# untitled.net
KiCad netlist of a schematic drawn in EAGLE
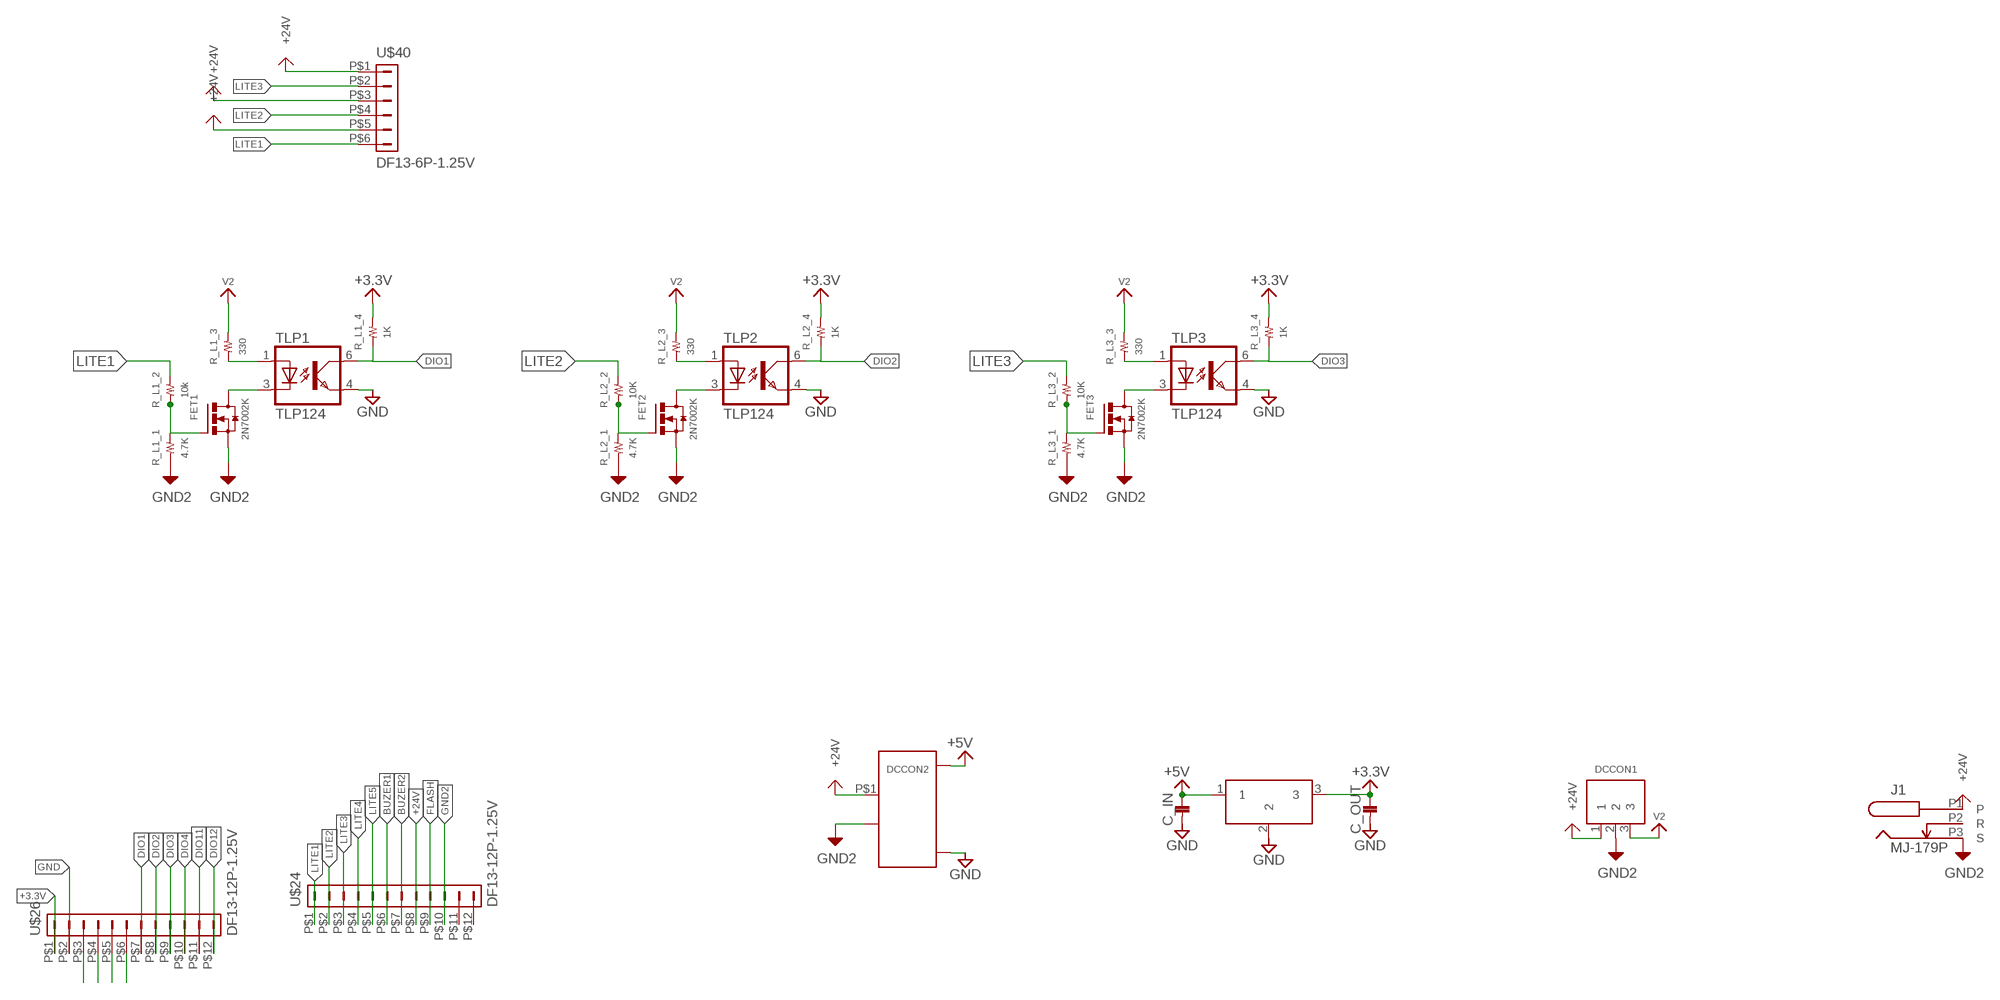
[diagram p0: schematic, sheet 1]

(export (version "E")
  (design (tool "Eeschema 10.0.6"))
  (components
    (comp (ref "C_IN")
      (value "1608")
      (footprint "eagle-import:1608")
      (libsource (lib "eagle-import") (part "1608"))
    )
    (comp (ref "C_OUT")
      (value "1608")
      (footprint "eagle-import:1608")
      (libsource (lib "eagle-import") (part "1608"))
    )
    (comp (ref "DCCON1")
      (value "Ｒ－７８Ｅ５．０")
      (footprint "eagle-import:Ｒ－７８Ｅ５．０")
      (libsource (lib "eagle-import") (part "Ｒ－７８Ｅ５．０"))
    )
    (comp (ref "DCCON2")
      (value "MAU100")
      (footprint "eagle-import:MAU")
      (libsource (lib "eagle-import") (part "MAU100"))
    )
    (comp (ref "FET1")
      (value "2N7002K")
      (footprint "eagle-import:SOT23")
      (libsource (lib "eagle-import") (part "CHIP_FET"))
    )
    (comp (ref "FET2")
      (value "2N7002K")
      (footprint "eagle-import:SOT23")
      (libsource (lib "eagle-import") (part "CHIP_FET"))
    )
    (comp (ref "FET3")
      (value "2N7002K")
      (footprint "eagle-import:SOT23")
      (libsource (lib "eagle-import") (part "CHIP_FET"))
    )
    (comp (ref "J1")
      (value "MJ-179P")
      (footprint "eagle-import:MJ-179P")
      (libsource (lib "eagle-import") (part "MJ-179P"))
    )
    (comp (ref "REGULATOR")
      (value "NJM2845")
      (footprint "eagle-import:TO252")
      (libsource (lib "eagle-import") (part "NJM2845"))
    )
    (comp (ref "R_L1_1")
      (value "4.7K")
      (footprint "eagle-import:1608")
      (libsource (lib "eagle-import") (part "RESISTOR__SMD"))
    )
    (comp (ref "R_L1_2")
      (value "10k")
      (footprint "eagle-import:1608")
      (libsource (lib "eagle-import") (part "RESISTOR__SMD"))
    )
    (comp (ref "R_L1_3")
      (value "330")
      (footprint "eagle-import:1608")
      (libsource (lib "eagle-import") (part "RESISTOR__SMD"))
    )
    (comp (ref "R_L1_4")
      (value "1K")
      (footprint "eagle-import:1608")
      (libsource (lib "eagle-import") (part "RESISTOR__SMD"))
    )
    (comp (ref "R_L2_1")
      (value "4.7K")
      (footprint "eagle-import:1608")
      (libsource (lib "eagle-import") (part "RESISTOR__SMD"))
    )
    (comp (ref "R_L2_2")
      (value "10K")
      (footprint "eagle-import:1608")
      (libsource (lib "eagle-import") (part "RESISTOR__SMD"))
    )
    (comp (ref "R_L2_3")
      (value "330")
      (footprint "eagle-import:1608")
      (libsource (lib "eagle-import") (part "RESISTOR__SMD"))
    )
    (comp (ref "R_L2_4")
      (value "1K")
      (footprint "eagle-import:1608")
      (libsource (lib "eagle-import") (part "RESISTOR__SMD"))
    )
    (comp (ref "R_L3_1")
      (value "4.7K")
      (footprint "eagle-import:1608")
      (libsource (lib "eagle-import") (part "RESISTOR__SMD"))
    )
    (comp (ref "R_L3_2")
      (value "10K")
      (footprint "eagle-import:1608")
      (libsource (lib "eagle-import") (part "RESISTOR__SMD"))
    )
    (comp (ref "R_L3_3")
      (value "330")
      (footprint "eagle-import:1608")
      (libsource (lib "eagle-import") (part "RESISTOR__SMD"))
    )
    (comp (ref "R_L3_4")
      (value "1K")
      (footprint "eagle-import:1608")
      (libsource (lib "eagle-import") (part "RESISTOR__SMD"))
    )
    (comp (ref "TLP1")
      (value "TLP124")
      (footprint "eagle-import:11−4C1")
      (libsource (lib "eagle-import") (part "TLP124"))
    )
    (comp (ref "TLP2")
      (value "TLP124")
      (footprint "eagle-import:11−4C1")
      (libsource (lib "eagle-import") (part "TLP124"))
    )
    (comp (ref "TLP3")
      (value "TLP124")
      (footprint "eagle-import:11−4C1")
      (libsource (lib "eagle-import") (part "TLP124"))
    )
    (comp (ref "U$24")
      (value "DF13-12P-1.25V")
      (footprint "eagle-import:DF13C-12P-1.25V")
      (libsource (lib "eagle-import") (part "DF13-12P-1.25V"))
    )
    (comp (ref "U$26")
      (value "DF13-12P-1.25V")
      (footprint "eagle-import:DF13C-12P-1.25V")
      (libsource (lib "eagle-import") (part "DF13-12P-1.25V"))
    )
    (comp (ref "U$40")
      (value "DF13-6P-1.25V")
      (footprint "eagle-import:DF13C-6P-1.25V")
      (libsource (lib "eagle-import") (part "DF13-6P-1.25V"))
    )
  )
  (nets
    (net (code "1") (name "+3.3V") (class "Default")
      (node (ref "C_OUT") (pin "P$1") (pinfunction "1_P$1") (pintype "passive"))
      (node (ref "REGULATOR") (pin "3") (pinfunction "3_3") (pintype "power_in"))
      (node (ref "R_L1_4") (pin "2") (pinfunction "P$2_2") (pintype "passive"))
      (node (ref "R_L2_4") (pin "2") (pinfunction "P$2_2") (pintype "passive"))
      (node (ref "R_L3_4") (pin "2") (pinfunction "P$2_2") (pintype "passive"))
      (node (ref "U$26") (pin "P$1") (pinfunction "1_P$1") (pintype "passive"))
    )
    (net (code "2") (name "+5V") (class "Default")
      (node (ref "C_IN") (pin "P$1") (pinfunction "1_P$1") (pintype "passive"))
      (node (ref "DCCON2") (pin "P$3") (pinfunction "VO+_P$3") (pintype "bidirectional"))
      (node (ref "REGULATOR") (pin "1") (pinfunction "1_1") (pintype "power_in"))
    )
    (net (code "3") (name "+24V") (class "Default")
      (node (ref "DCCON1") (pin "1") (pinfunction "1_1") (pintype "bidirectional"))
      (node (ref "DCCON2") (pin "P$1") (pinfunction "VIN+_P$1") (pintype "bidirectional"))
      (node (ref "J1") (pin "P1") (pinfunction "P_P1") (pintype "power_in"))
      (node (ref "U$24") (pin "P$8") (pinfunction "8_P$8") (pintype "passive"))
      (node (ref "U$40") (pin "P$1") (pinfunction "1_P$1") (pintype "passive"))
      (node (ref "U$40") (pin "P$3") (pinfunction "3_P$3") (pintype "passive"))
      (node (ref "U$40") (pin "P$5") (pinfunction "5_P$5") (pintype "passive"))
    )
    (net (code "4") (name "BUZER1") (class "Default")
      (node (ref "U$24") (pin "P$6") (pinfunction "6_P$6") (pintype "passive"))
    )
    (net (code "5") (name "BUZER2") (class "Default")
      (node (ref "U$24") (pin "P$7") (pinfunction "7_P$7") (pintype "passive"))
    )
    (net (code "6") (name "DIO1") (class "Default")
      (node (ref "R_L1_4") (pin "1") (pinfunction "P$1_1") (pintype "passive"))
      (node (ref "TLP1") (pin "6") (pinfunction "COL_6") (pintype "passive"))
      (node (ref "U$26") (pin "P$7") (pinfunction "7_P$7") (pintype "passive"))
    )
    (net (code "7") (name "DIO2") (class "Default")
      (node (ref "R_L2_4") (pin "1") (pinfunction "P$1_1") (pintype "passive"))
      (node (ref "TLP2") (pin "6") (pinfunction "COL_6") (pintype "passive"))
      (node (ref "U$26") (pin "P$8") (pinfunction "8_P$8") (pintype "passive"))
    )
    (net (code "8") (name "DIO3") (class "Default")
      (node (ref "R_L3_4") (pin "1") (pinfunction "P$1_1") (pintype "passive"))
      (node (ref "TLP3") (pin "6") (pinfunction "COL_6") (pintype "passive"))
      (node (ref "U$26") (pin "P$9") (pinfunction "9_P$9") (pintype "passive"))
    )
    (net (code "9") (name "DIO4") (class "Default")
      (node (ref "U$26") (pin "P$10") (pinfunction "10_P$10") (pintype "passive"))
    )
    (net (code "10") (name "DIO11") (class "Default")
      (node (ref "U$26") (pin "P$11") (pinfunction "11_P$11") (pintype "passive"))
    )
    (net (code "11") (name "DIO12") (class "Default")
      (node (ref "U$26") (pin "P$12") (pinfunction "12_P$12") (pintype "passive"))
    )
    (net (code "12") (name "FLASH") (class "Default")
      (node (ref "U$24") (pin "P$9") (pinfunction "9_P$9") (pintype "passive"))
    )
    (net (code "13") (name "GND") (class "Default")
      (node (ref "C_IN") (pin "P$2") (pinfunction "2_P$2") (pintype "passive"))
      (node (ref "C_OUT") (pin "P$2") (pinfunction "2_P$2") (pintype "passive"))
      (node (ref "DCCON2") (pin "P$5") (pinfunction "VO-_P$5") (pintype "bidirectional"))
      (node (ref "REGULATOR") (pin "2") (pinfunction "2_2") (pintype "power_in"))
      (node (ref "TLP1") (pin "4") (pinfunction "EMIT_4") (pintype "passive"))
      (node (ref "TLP2") (pin "4") (pinfunction "EMIT_4") (pintype "passive"))
      (node (ref "TLP3") (pin "4") (pinfunction "EMIT_4") (pintype "passive"))
      (node (ref "U$26") (pin "P$2") (pinfunction "2_P$2") (pintype "passive"))
    )
    (net (code "14") (name "GND2") (class "Default")
      (node (ref "DCCON1") (pin "2") (pinfunction "2_2") (pintype "bidirectional"))
      (node (ref "DCCON2") (pin "P$2") (pinfunction "VIN-_P$2") (pintype "bidirectional"))
      (node (ref "FET1") (pin "2") (pinfunction "S_2") (pintype "passive"))
      (node (ref "FET2") (pin "2") (pinfunction "S_2") (pintype "passive"))
      (node (ref "FET3") (pin "2") (pinfunction "S_2") (pintype "passive"))
      (node (ref "J1") (pin "P3") (pinfunction "S_P3") (pintype "power_in"))
      (node (ref "R_L1_1") (pin "1") (pinfunction "P$1_1") (pintype "passive"))
      (node (ref "R_L2_1") (pin "1") (pinfunction "P$1_1") (pintype "passive"))
      (node (ref "R_L3_1") (pin "1") (pinfunction "P$1_1") (pintype "passive"))
      (node (ref "U$24") (pin "P$10") (pinfunction "10_P$10") (pintype "passive"))
    )
    (net (code "15") (name "LITE1") (class "Default")
      (node (ref "R_L1_2") (pin "2") (pinfunction "P$2_2") (pintype "passive"))
      (node (ref "U$24") (pin "P$1") (pinfunction "1_P$1") (pintype "passive"))
      (node (ref "U$40") (pin "P$6") (pinfunction "6_P$6") (pintype "passive"))
    )
    (net (code "16") (name "LITE2") (class "Default")
      (node (ref "R_L2_2") (pin "2") (pinfunction "P$2_2") (pintype "passive"))
      (node (ref "U$24") (pin "P$2") (pinfunction "2_P$2") (pintype "passive"))
      (node (ref "U$40") (pin "P$4") (pinfunction "4_P$4") (pintype "passive"))
    )
    (net (code "17") (name "LITE3") (class "Default")
      (node (ref "R_L3_2") (pin "2") (pinfunction "P$2_2") (pintype "passive"))
      (node (ref "U$24") (pin "P$3") (pinfunction "3_P$3") (pintype "passive"))
      (node (ref "U$40") (pin "P$2") (pinfunction "2_P$2") (pintype "passive"))
    )
    (net (code "18") (name "LITE4") (class "Default")
      (node (ref "U$24") (pin "P$4") (pinfunction "4_P$4") (pintype "passive"))
    )
    (net (code "19") (name "LITE5") (class "Default")
      (node (ref "U$24") (pin "P$5") (pinfunction "5_P$5") (pintype "passive"))
    )
    (net (code "20") (name "Net-(FET1-D)") (class "Default")
      (node (ref "FET1") (pin "3") (pinfunction "D_3") (pintype "passive"))
      (node (ref "TLP1") (pin "3") (pinfunction "C_3") (pintype "passive"))
    )
    (net (code "21") (name "Net-(FET1-G)") (class "Default")
      (node (ref "FET1") (pin "1") (pinfunction "G_1") (pintype "passive"))
      (node (ref "R_L1_1") (pin "2") (pinfunction "P$2_2") (pintype "passive"))
      (node (ref "R_L1_2") (pin "1") (pinfunction "P$1_1") (pintype "passive"))
    )
    (net (code "22") (name "Net-(FET2-D)") (class "Default")
      (node (ref "FET2") (pin "3") (pinfunction "D_3") (pintype "passive"))
      (node (ref "TLP2") (pin "3") (pinfunction "C_3") (pintype "passive"))
    )
    (net (code "23") (name "Net-(FET2-G)") (class "Default")
      (node (ref "FET2") (pin "1") (pinfunction "G_1") (pintype "passive"))
      (node (ref "R_L2_1") (pin "2") (pinfunction "P$2_2") (pintype "passive"))
      (node (ref "R_L2_2") (pin "1") (pinfunction "P$1_1") (pintype "passive"))
    )
    (net (code "24") (name "Net-(FET3-D)") (class "Default")
      (node (ref "FET3") (pin "3") (pinfunction "D_3") (pintype "passive"))
      (node (ref "TLP3") (pin "3") (pinfunction "C_3") (pintype "passive"))
    )
    (net (code "25") (name "Net-(FET3-G)") (class "Default")
      (node (ref "FET3") (pin "1") (pinfunction "G_1") (pintype "passive"))
      (node (ref "R_L3_1") (pin "2") (pinfunction "P$2_2") (pintype "passive"))
      (node (ref "R_L3_2") (pin "1") (pinfunction "P$1_1") (pintype "passive"))
    )
    (net (code "26") (name "Net-(R_L1_3-P$1)") (class "Default")
      (node (ref "R_L1_3") (pin "1") (pinfunction "P$1_1") (pintype "passive"))
      (node (ref "TLP1") (pin "1") (pinfunction "A_1") (pintype "passive"))
    )
    (net (code "27") (name "Net-(R_L2_3-P$1)") (class "Default")
      (node (ref "R_L2_3") (pin "1") (pinfunction "P$1_1") (pintype "passive"))
      (node (ref "TLP2") (pin "1") (pinfunction "A_1") (pintype "passive"))
    )
    (net (code "28") (name "Net-(R_L3_3-P$1)") (class "Default")
      (node (ref "R_L3_3") (pin "1") (pinfunction "P$1_1") (pintype "passive"))
      (node (ref "TLP3") (pin "1") (pinfunction "A_1") (pintype "passive"))
    )
    (net (code "29") (name "V2") (class "Default")
      (node (ref "DCCON1") (pin "3") (pinfunction "3_3") (pintype "bidirectional"))
      (node (ref "R_L1_3") (pin "2") (pinfunction "P$2_2") (pintype "passive"))
      (node (ref "R_L2_3") (pin "2") (pinfunction "P$2_2") (pintype "passive"))
      (node (ref "R_L3_3") (pin "2") (pinfunction "P$2_2") (pintype "passive"))
    )
    (net (code "30") (name "unconnected-(J1-R-PadP2)") (class "Default")
      (node (ref "J1") (pin "P2") (pinfunction "R_P2") (pintype "input"))
    )
    (net (code "31") (name "unconnected-(U$24-11-PadP$11)") (class "Default")
      (node (ref "U$24") (pin "P$11") (pinfunction "11_P$11") (pintype "passive"))
    )
    (net (code "32") (name "unconnected-(U$24-12-PadP$12)") (class "Default")
      (node (ref "U$24") (pin "P$12") (pinfunction "12_P$12") (pintype "passive"))
    )
    (net (code "33") (name "unconnected-(U$26-3-PadP$3)") (class "Default")
      (node (ref "U$26") (pin "P$3") (pinfunction "3_P$3") (pintype "passive"))
    )
    (net (code "34") (name "unconnected-(U$26-4-PadP$4)") (class "Default")
      (node (ref "U$26") (pin "P$4") (pinfunction "4_P$4") (pintype "passive"))
    )
    (net (code "35") (name "unconnected-(U$26-5-PadP$5)") (class "Default")
      (node (ref "U$26") (pin "P$5") (pinfunction "5_P$5") (pintype "passive"))
    )
    (net (code "36") (name "unconnected-(U$26-6-PadP$6)") (class "Default")
      (node (ref "U$26") (pin "P$6") (pinfunction "6_P$6") (pintype "passive"))
    )
  )
)
